# battery_V1_1.net
KiCad netlist of a schematic drawn in EAGLE
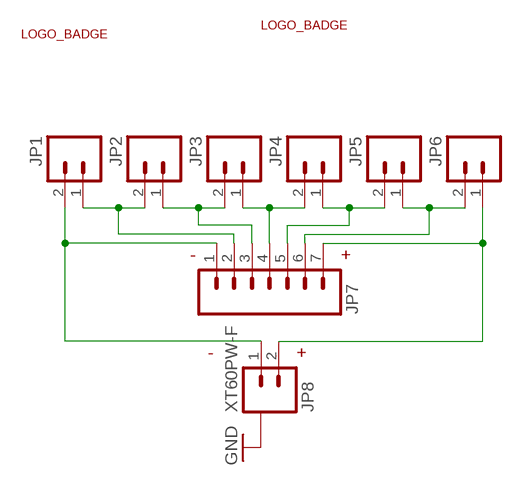
[diagram p0: schematic, sheet 1]

(export (version "E")
  (design (tool "Eeschema 10.0.6"))
  (components
    (comp (ref "JP1")
      (value "M02_PH2.0_Z")
      (footprint "eagle-import:PH2.0_2Z")
      (libsource (lib "eagle-import") (part "M02_PH2.0_Z"))
    )
    (comp (ref "JP2")
      (value "M02_PH2.0_Z")
      (footprint "eagle-import:PH2.0_2Z")
      (libsource (lib "eagle-import") (part "M02_PH2.0_Z"))
    )
    (comp (ref "JP3")
      (value "M02_PH2.0_Z")
      (footprint "eagle-import:PH2.0_2Z")
      (libsource (lib "eagle-import") (part "M02_PH2.0_Z"))
    )
    (comp (ref "JP4")
      (value "M02_PH2.0_Z")
      (footprint "eagle-import:PH2.0_2Z")
      (libsource (lib "eagle-import") (part "M02_PH2.0_Z"))
    )
    (comp (ref "JP5")
      (value "M02_PH2.0_Z")
      (footprint "eagle-import:PH2.0_2Z")
      (libsource (lib "eagle-import") (part "M02_PH2.0_Z"))
    )
    (comp (ref "JP6")
      (value "M02_PH2.0_Z")
      (footprint "eagle-import:PH2.0_2Z")
      (libsource (lib "eagle-import") (part "M02_PH2.0_Z"))
    )
    (comp (ref "JP7")
      (value "M07_XH2.54_7Z")
      (footprint "eagle-import:XH2.54_7Z")
      (libsource (lib "eagle-import") (part "M07_XH2.54_7Z"))
    )
    (comp (ref "JP8")
      (value "XT60PW-F")
      (footprint "eagle-import:XT60PW-F")
      (libsource (lib "eagle-import") (part "M02_G_XT60PW-F"))
    )
    (comp (ref "U1")
      (value "LOGO_BADGE_24.3_20_S")
      (footprint "eagle-import:LOGO_BADGE_24.3_20_S")
      (libsource (lib "eagle-import") (part "LOGO_BADGE_24.3_20_S"))
    )
    (comp (ref "U2")
      (value "LOGO_BADGE_12.2_9.5_S")
      (footprint "eagle-import:LOGO_BADGE_12.2_9.5_S")
      (libsource (lib "eagle-import") (part "LOGO_BADGE_12.2_9.5_S"))
    )
  )
  (nets
    (net (code "1") (name "GND") (class "Default")
      (node (ref "JP8") (pin "P$1") (pinfunction "G_P$1") (pintype "power_in"))
      (node (ref "JP8") (pin "P$2") (pinfunction "G_P$2") (pintype "power_in"))
      (node (ref "JP8") (pin "P$3") (pinfunction "G_P$3") (pintype "power_in"))
      (node (ref "JP8") (pin "P$4") (pinfunction "G_P$4") (pintype "power_in"))
    )
    (net (code "2") (name "Net-(JP1-Pad1)") (class "Default")
      (node (ref "JP1") (pin "1") (pinfunction "1_1") (pintype "passive"))
      (node (ref "JP2") (pin "2") (pinfunction "2_2") (pintype "passive"))
      (node (ref "JP7") (pin "2") (pinfunction "2_2") (pintype "passive"))
    )
    (net (code "3") (name "Net-(JP1-Pad2)") (class "Default")
      (node (ref "JP1") (pin "2") (pinfunction "2_2") (pintype "passive"))
      (node (ref "JP7") (pin "1") (pinfunction "1_1") (pintype "passive"))
      (node (ref "JP8") (pin "1") (pinfunction "1_1") (pintype "passive"))
    )
    (net (code "4") (name "Net-(JP2-Pad1)") (class "Default")
      (node (ref "JP2") (pin "1") (pinfunction "1_1") (pintype "passive"))
      (node (ref "JP3") (pin "2") (pinfunction "2_2") (pintype "passive"))
      (node (ref "JP7") (pin "3") (pinfunction "3_3") (pintype "passive"))
    )
    (net (code "5") (name "Net-(JP3-Pad1)") (class "Default")
      (node (ref "JP3") (pin "1") (pinfunction "1_1") (pintype "passive"))
      (node (ref "JP4") (pin "2") (pinfunction "2_2") (pintype "passive"))
      (node (ref "JP7") (pin "4") (pinfunction "4_4") (pintype "passive"))
    )
    (net (code "6") (name "Net-(JP4-Pad1)") (class "Default")
      (node (ref "JP4") (pin "1") (pinfunction "1_1") (pintype "passive"))
      (node (ref "JP5") (pin "2") (pinfunction "2_2") (pintype "passive"))
      (node (ref "JP7") (pin "5") (pinfunction "5_5") (pintype "passive"))
    )
    (net (code "7") (name "Net-(JP5-Pad1)") (class "Default")
      (node (ref "JP5") (pin "1") (pinfunction "1_1") (pintype "passive"))
      (node (ref "JP6") (pin "2") (pinfunction "2_2") (pintype "passive"))
      (node (ref "JP7") (pin "6") (pinfunction "6_6") (pintype "passive"))
    )
    (net (code "8") (name "Net-(JP6-Pad1)") (class "Default")
      (node (ref "JP6") (pin "1") (pinfunction "1_1") (pintype "passive"))
      (node (ref "JP7") (pin "7") (pinfunction "7_7") (pintype "passive"))
      (node (ref "JP8") (pin "2") (pinfunction "2_2") (pintype "passive"))
    )
  )
)
